# GZ7_1_x-ULN2003.net
KiCad netlist of a schematic drawn in Altium Designer
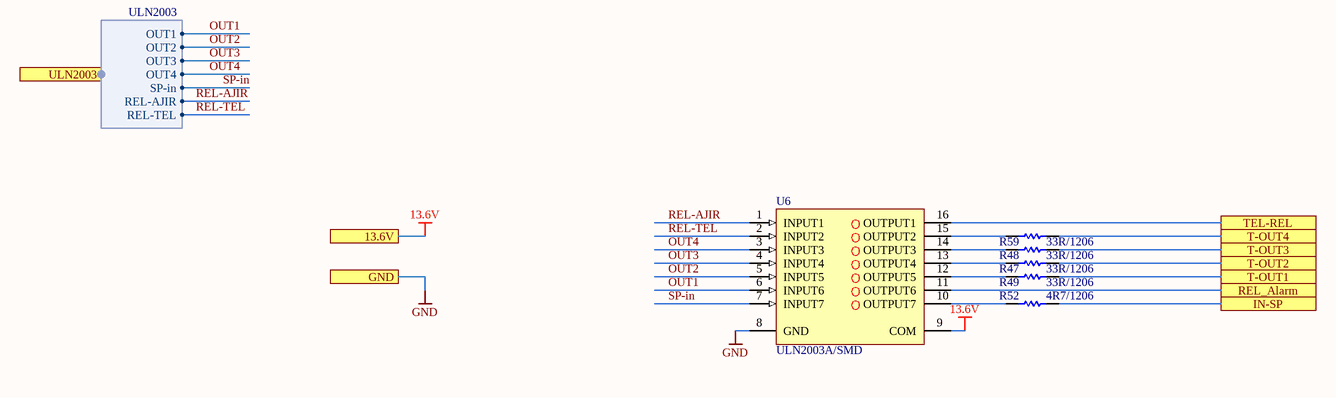
[diagram p0: GZ7_1_x-ULN2003.SchDoc]

(export (version "E")
  (design (tool "Eeschema 10.0.6"))
  (components
    (comp (ref "R47")
      (value "33R/1206")
      (footprint "my1206")
      (description "RES 1206")
      (fields (field (name "DESIGNER") "Abbas Basereh"))
      (libsource (lib "Altium") (part "RES 1206 0.25W"))
    )
    (comp (ref "R48")
      (value "33R/1206")
      (footprint "MY1206")
      (description "RES 1206")
      (fields (field (name "DESIGNER") "Abbas Basereh"))
      (libsource (lib "Altium") (part "RES 1206 0.25W"))
    )
    (comp (ref "R49")
      (value "33R/1206")
      (footprint "my1206")
      (description "RES 1206")
      (fields (field (name "DESIGNER") "Abbas Basereh"))
      (libsource (lib "Altium") (part "RES 1206 0.25W"))
    )
    (comp (ref "R52")
      (value "4R7/1206")
      (footprint "RES-(1/2)DS")
      (description "RES Axial 1/4W")
      (fields (field (name "DESIGNER") "Abbas Basereh"))
      (libsource (lib "Altium") (part "RES Axial 0.5W"))
    )
    (comp (ref "R59")
      (value "33R/1206")
      (footprint "MY1206")
      (description "RES 1206")
      (fields (field (name "DESIGNER") "Abbas Basereh"))
      (libsource (lib "Altium") (part "RES 1206 0.25W"))
    )
    (comp (ref "U6") (value "ULN2003A/SMD") (footprint "SO-16") (libsource (lib "Altium") (part "ULN2003A")))
  )
  (nets
    (net (code "2") (name "/IN-SP") (class "Default")
      (node (ref "R52") (pin "2") (pinfunction "2_2") (pintype "passive"))
    )
    (net (code "3") (name "/OUT1") (class "Default")
      (node (ref "U6") (pin "6") (pinfunction "INPUT6_6") (pintype "input"))
    )
    (net (code "4") (name "/OUT2") (class "Default")
      (node (ref "U6") (pin "5") (pinfunction "INPUT5_5") (pintype "input"))
    )
    (net (code "5") (name "/OUT3") (class "Default")
      (node (ref "U6") (pin "4") (pinfunction "INPUT4_4") (pintype "input"))
    )
    (net (code "6") (name "/OUT4") (class "Default")
      (node (ref "U6") (pin "3") (pinfunction "INPUT3_3") (pintype "input"))
    )
    (net (code "7") (name "/REL-AJIR") (class "Default")
      (node (ref "U6") (pin "1") (pinfunction "INPUT1_1") (pintype "input"))
    )
    (net (code "8") (name "/REL-TEL") (class "Default")
      (node (ref "U6") (pin "2") (pinfunction "INPUT2_2") (pintype "input"))
    )
    (net (code "9") (name "/REL_Alarm") (class "Default")
      (node (ref "U6") (pin "11") (pinfunction "OUTPUT6_11") (pintype "passive"))
    )
    (net (code "10") (name "/SP-in") (class "Default")
      (node (ref "U6") (pin "7") (pinfunction "INPUT7_7") (pintype "input"))
    )
    (net (code "11") (name "/T-OUT1") (class "Default")
      (node (ref "R49") (pin "2") (pinfunction "2_2") (pintype "passive"))
    )
    (net (code "12") (name "/T-OUT2") (class "Default")
      (node (ref "R47") (pin "2") (pinfunction "2_2") (pintype "passive"))
    )
    (net (code "13") (name "/T-OUT3") (class "Default")
      (node (ref "R48") (pin "2") (pinfunction "2_2") (pintype "passive"))
    )
    (net (code "14") (name "/T-OUT4") (class "Default")
      (node (ref "R59") (pin "2") (pinfunction "2_2") (pintype "passive"))
    )
    (net (code "15") (name "/TEL-REL") (class "Default")
      (node (ref "U6") (pin "16") (pinfunction "OUTPUT1_16") (pintype "passive"))
    )
    (net (code "17") (name "13.6V") (class "Default")
      (node (ref "U6") (pin "9") (pinfunction "COM_9") (pintype "power_in"))
    )
    (net (code "18") (name "GND") (class "Default")
      (node (ref "U6") (pin "8") (pinfunction "GND_8") (pintype "power_in"))
    )
    (net (code "19") (name "Net-(U6-OUTPUT2)") (class "Default")
      (node (ref "R59") (pin "1") (pinfunction "1_1") (pintype "passive"))
      (node (ref "U6") (pin "15") (pinfunction "OUTPUT2_15") (pintype "passive"))
    )
    (net (code "20") (name "Net-(U6-OUTPUT3)") (class "Default")
      (node (ref "R48") (pin "1") (pinfunction "1_1") (pintype "passive"))
      (node (ref "U6") (pin "14") (pinfunction "OUTPUT3_14") (pintype "passive"))
    )
    (net (code "21") (name "Net-(U6-OUTPUT4)") (class "Default")
      (node (ref "R47") (pin "1") (pinfunction "1_1") (pintype "passive"))
      (node (ref "U6") (pin "13") (pinfunction "OUTPUT4_13") (pintype "passive"))
    )
    (net (code "22") (name "Net-(U6-OUTPUT5)") (class "Default")
      (node (ref "R49") (pin "1") (pinfunction "1_1") (pintype "passive"))
      (node (ref "U6") (pin "12") (pinfunction "OUTPUT5_12") (pintype "passive"))
    )
    (net (code "23") (name "Net-(U6-OUTPUT7)") (class "Default")
      (node (ref "R52") (pin "1") (pinfunction "1_1") (pintype "passive"))
      (node (ref "U6") (pin "10") (pinfunction "OUTPUT7_10") (pintype "passive"))
    )
  )
)
